# PantherZVS.net
KiCad netlist of a schematic drawn in Altium Designer
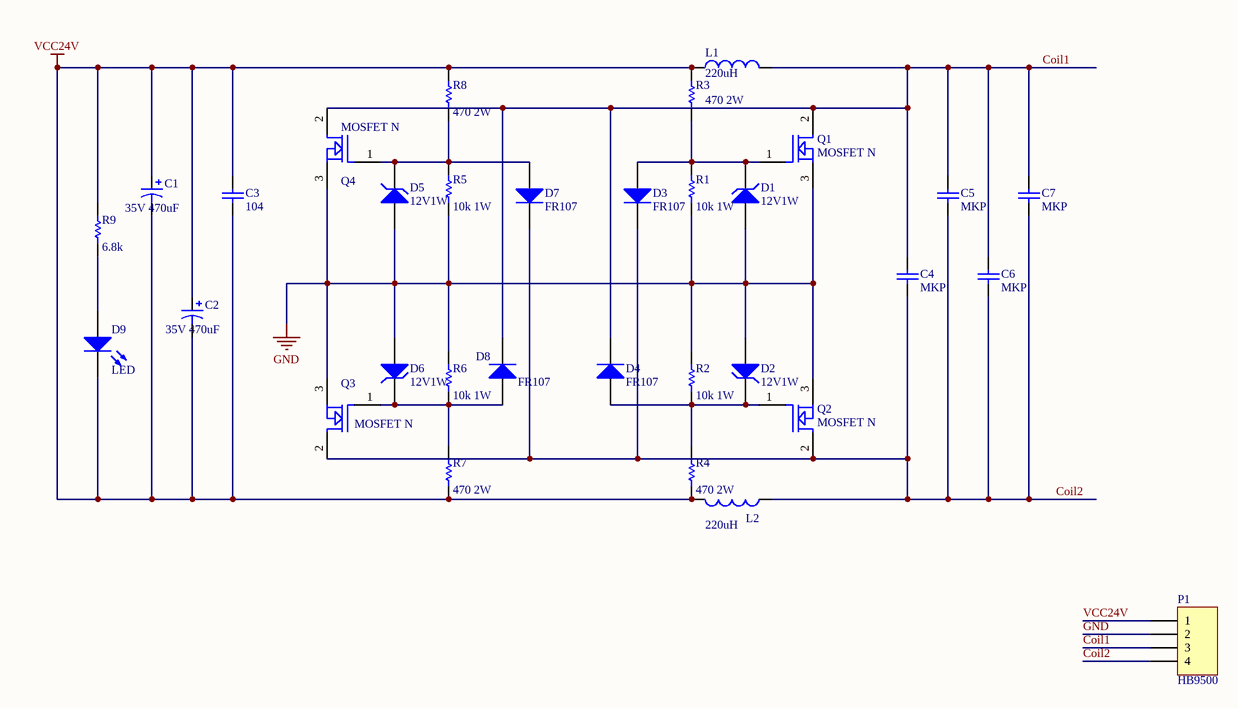
[diagram p0: PantherZVS.SchDoc]

(export (version "E")
  (design (tool "Eeschema 10.0.6"))
  (components
    (comp (ref "C1")
      (value "35V 470uF")
      (footprint "C4_5_10mm")
      (description "Polarized Capacitor (Radial)")
      (fields (field (name "PUBLISHER") "Altium Limited"))
      (libsource (lib "Miscellaneous Devices") (part "Cap Pol1"))
    )
    (comp (ref "C2")
      (value "35V 470uF")
      (footprint "C4_5_10mm")
      (description "Polarized Capacitor (Radial)")
      (fields (field (name "PUBLISHER") "Altium Limited"))
      (libsource (lib "Miscellaneous Devices") (part "Cap Pol1"))
    )
    (comp (ref "C3")
      (value "104")
      (footprint "RAD-0.3")
      (description "Capacitor")
      (fields (field (name "PUBLISHER") "Altium Limited"))
      (libsource (lib "Miscellaneous Devices") (part "Cap"))
    )
    (comp (ref "C4")
      (value "MKP")
      (footprint "MKP_Capacitor")
      (description "Capacitor")
      (fields (field (name "PUBLISHER") "Altium Limited"))
      (libsource (lib "Miscellaneous Devices") (part "Cap"))
    )
    (comp (ref "C5")
      (value "MKP")
      (footprint "MKP_Capacitor")
      (description "Capacitor")
      (fields (field (name "PUBLISHER") "Altium Limited"))
      (libsource (lib "Miscellaneous Devices") (part "Cap"))
    )
    (comp (ref "C6")
      (value "MKP")
      (footprint "MKP_Capacitor")
      (description "Capacitor")
      (fields (field (name "PUBLISHER") "Altium Limited"))
      (libsource (lib "Miscellaneous Devices") (part "Cap"))
    )
    (comp (ref "C7")
      (value "MKP")
      (footprint "MKP_Capacitor")
      (description "Capacitor")
      (fields (field (name "PUBLISHER") "Altium Limited"))
      (libsource (lib "Miscellaneous Devices") (part "Cap"))
    )
    (comp (ref "D1")
      (value "12V1W")
      (footprint "DIODE-0.4")
      (description "Zener Diode")
      (fields (field (name "PUBLISHER") "Altium Limited"))
      (libsource (lib "Miscellaneous Devices") (part "D Zener"))
    )
    (comp (ref "D2")
      (value "12V1W")
      (footprint "DIODE-0.4")
      (description "Zener Diode")
      (fields (field (name "PUBLISHER") "Altium Limited"))
      (libsource (lib "Miscellaneous Devices") (part "D Zener"))
    )
    (comp (ref "D3")
      (value "FR107")
      (footprint "DIODE-0.4")
      (description "1 Amp General Purpose Rectifier")
      (fields (field (name "PUBLISHER") "Altium Limited"))
      (libsource (lib "Miscellaneous Devices") (part "Diode 1N4001"))
    )
    (comp (ref "D4")
      (value "FR107")
      (footprint "DIODE-0.4")
      (description "1 Amp General Purpose Rectifier")
      (fields (field (name "PUBLISHER") "Altium Limited"))
      (libsource (lib "Miscellaneous Devices") (part "Diode 1N4001"))
    )
    (comp (ref "D5")
      (value "12V1W")
      (footprint "DIODE-0.4")
      (description "Zener Diode")
      (fields (field (name "PUBLISHER") "Altium Limited"))
      (libsource (lib "Miscellaneous Devices") (part "D Zener"))
    )
    (comp (ref "D6")
      (value "12V1W")
      (footprint "DIODE-0.4")
      (description "Zener Diode")
      (fields (field (name "PUBLISHER") "Altium Limited"))
      (libsource (lib "Miscellaneous Devices") (part "D Zener"))
    )
    (comp (ref "D7")
      (value "FR107")
      (footprint "DIODE-0.4")
      (description "1 Amp General Purpose Rectifier")
      (fields (field (name "PUBLISHER") "Altium Limited"))
      (libsource (lib "Miscellaneous Devices") (part "Diode 1N4001"))
    )
    (comp (ref "D8")
      (value "FR107")
      (footprint "DIODE-0.4")
      (description "1 Amp General Purpose Rectifier")
      (fields (field (name "PUBLISHER") "Altium Limited"))
      (libsource (lib "Miscellaneous Devices") (part "Diode 1N4001"))
    )
    (comp (ref "D9")
      (value "LED")
      (footprint "0805")
      (description "Typical INFRARED GaAs LED")
      (fields (field (name "PUBLISHER") "Altium Limited"))
      (libsource (lib "Miscellaneous Devices") (part "LED0"))
    )
    (comp (ref "L1")
      (value "220uH")
      (footprint "HBL_30_10_H")
      (description "Inductor")
      (fields (field (name "PUBLISHER") "Altium Limited"))
      (libsource (lib "Miscellaneous Devices") (part "Inductor"))
    )
    (comp (ref "L2")
      (value "220uH")
      (footprint "HBL_30_10_H")
      (description "Inductor")
      (fields (field (name "PUBLISHER") "Altium Limited"))
      (libsource (lib "Miscellaneous Devices") (part "Inductor"))
    )
    (comp (ref "P1")
      (value "HB9500")
      (footprint "HB9500_4P")
      (description "Header, 4-Pin")
      (fields (field (name "PUBLISHER") "Altium Limited"))
      (libsource (lib "Miscellaneous Connectors") (part "Header 4"))
    )
    (comp (ref "Q1")
      (value "MOSFET N")
      (footprint "TO-247AC_ZCEDGE")
      (libsource (lib "场效应管及可控硅") (part "MOSFET N"))
    )
    (comp (ref "Q2")
      (value "MOSFET N")
      (footprint "TO-247AC_ZCEDGE")
      (libsource (lib "场效应管及可控硅") (part "MOSFET N"))
    )
    (comp (ref "Q3")
      (value "MOSFET N")
      (footprint "TO-247AC_ZCEDGE")
      (libsource (lib "场效应管及可控硅") (part "MOSFET N"))
    )
    (comp (ref "Q4")
      (value "MOSFET N")
      (footprint "TO-247AC_ZCEDGE")
      (libsource (lib "场效应管及可控硅") (part "MOSFET N"))
    )
    (comp (ref "R1")
      (value "10k 1W")
      (footprint "1WZC")
      (description "Resistor")
      (fields (field (name "PUBLISHER") "Altium Limited"))
      (libsource (lib "Miscellaneous Devices") (part "Res1"))
    )
    (comp (ref "R2")
      (value "10k 1W")
      (footprint "1WZC")
      (description "Resistor")
      (fields (field (name "PUBLISHER") "Altium Limited"))
      (libsource (lib "Miscellaneous Devices") (part "Res1"))
    )
    (comp (ref "R3")
      (value "470 2W")
      (footprint "1WZC")
      (description "Resistor")
      (fields (field (name "PUBLISHER") "Altium Limited"))
      (libsource (lib "Miscellaneous Devices") (part "Res1"))
    )
    (comp (ref "R4")
      (value "470 2W")
      (footprint "2WZC")
      (description "Resistor")
      (fields (field (name "PUBLISHER") "Altium Limited"))
      (libsource (lib "Miscellaneous Devices") (part "Res1"))
    )
    (comp (ref "R5")
      (value "10k 1W")
      (footprint "1WZC")
      (description "Resistor")
      (fields (field (name "PUBLISHER") "Altium Limited"))
      (libsource (lib "Miscellaneous Devices") (part "Res1"))
    )
    (comp (ref "R6")
      (value "10k 1W")
      (footprint "1WZC")
      (description "Resistor")
      (fields (field (name "PUBLISHER") "Altium Limited"))
      (libsource (lib "Miscellaneous Devices") (part "Res1"))
    )
    (comp (ref "R7")
      (value "470 2W")
      (footprint "2WZC")
      (description "Resistor")
      (fields (field (name "PUBLISHER") "Altium Limited"))
      (libsource (lib "Miscellaneous Devices") (part "Res1"))
    )
    (comp (ref "R8")
      (value "470 2W")
      (footprint "2WZC")
      (description "Resistor")
      (fields (field (name "PUBLISHER") "Altium Limited"))
      (libsource (lib "Miscellaneous Devices") (part "Res1"))
    )
    (comp (ref "R9")
      (value "6.8k")
      (footprint "AXIAL-0.3")
      (description "Resistor")
      (fields (field (name "PUBLISHER") "Altium Limited"))
      (libsource (lib "Miscellaneous Devices") (part "Res1"))
    )
  )
  (nets
    (net (code "1") (name "/Coil1") (class "Default")
      (node (ref "C4") (pin "2") (pinfunction "2_2") (pintype "passive"))
      (node (ref "C5") (pin "2") (pinfunction "2_2") (pintype "passive"))
      (node (ref "C6") (pin "2") (pinfunction "2_2") (pintype "passive"))
      (node (ref "C7") (pin "2") (pinfunction "2_2") (pintype "passive"))
      (node (ref "D4") (pin "2") (pinfunction "K_2") (pintype "passive"))
      (node (ref "D8") (pin "2") (pinfunction "K_2") (pintype "passive"))
      (node (ref "L1") (pin "2") (pinfunction "2_2") (pintype "passive"))
      (node (ref "P1") (pin "3") (pinfunction "3_3") (pintype "passive"))
      (node (ref "Q1") (pin "2") (pinfunction "D_2") (pintype "passive"))
      (node (ref "Q4") (pin "2") (pinfunction "D_2") (pintype "passive"))
    )
    (net (code "2") (name "/Coil2") (class "Default")
      (node (ref "C4") (pin "1") (pinfunction "1_1") (pintype "passive"))
      (node (ref "C5") (pin "1") (pinfunction "1_1") (pintype "passive"))
      (node (ref "C6") (pin "1") (pinfunction "1_1") (pintype "passive"))
      (node (ref "C7") (pin "1") (pinfunction "1_1") (pintype "passive"))
      (node (ref "D3") (pin "2") (pinfunction "K_2") (pintype "passive"))
      (node (ref "D7") (pin "2") (pinfunction "K_2") (pintype "passive"))
      (node (ref "L2") (pin "1") (pinfunction "1_1") (pintype "passive"))
      (node (ref "P1") (pin "4") (pinfunction "4_4") (pintype "passive"))
      (node (ref "Q2") (pin "2") (pinfunction "D_2") (pintype "passive"))
      (node (ref "Q3") (pin "2") (pinfunction "D_2") (pintype "passive"))
    )
    (net (code "3") (name "GND") (class "Default")
      (node (ref "D1") (pin "1") (pinfunction "A_1") (pintype "passive"))
      (node (ref "D2") (pin "1") (pinfunction "A_1") (pintype "passive"))
      (node (ref "D5") (pin "1") (pinfunction "A_1") (pintype "passive"))
      (node (ref "D6") (pin "1") (pinfunction "A_1") (pintype "passive"))
      (node (ref "P1") (pin "2") (pinfunction "2_2") (pintype "passive"))
      (node (ref "Q1") (pin "3") (pinfunction "S_3") (pintype "passive"))
      (node (ref "Q2") (pin "3") (pinfunction "S_3") (pintype "passive"))
      (node (ref "Q3") (pin "3") (pinfunction "S_3") (pintype "passive"))
      (node (ref "Q4") (pin "3") (pinfunction "S_3") (pintype "passive"))
      (node (ref "R1") (pin "1") (pinfunction "1_1") (pintype "passive"))
      (node (ref "R2") (pin "2") (pinfunction "2_2") (pintype "passive"))
      (node (ref "R5") (pin "2") (pinfunction "2_2") (pintype "passive"))
      (node (ref "R6") (pin "1") (pinfunction "1_1") (pintype "passive"))
    )
    (net (code "4") (name "Net-(D1-K)") (class "Default")
      (node (ref "D1") (pin "2") (pinfunction "K_2") (pintype "passive"))
      (node (ref "D3") (pin "1") (pinfunction "A_1") (pintype "passive"))
      (node (ref "Q1") (pin "1") (pinfunction "G_1") (pintype "passive"))
      (node (ref "R1") (pin "2") (pinfunction "2_2") (pintype "passive"))
      (node (ref "R3") (pin "1") (pinfunction "1_1") (pintype "passive"))
    )
    (net (code "5") (name "Net-(D2-K)") (class "Default")
      (node (ref "D2") (pin "2") (pinfunction "K_2") (pintype "passive"))
      (node (ref "D4") (pin "1") (pinfunction "A_1") (pintype "passive"))
      (node (ref "Q2") (pin "1") (pinfunction "G_1") (pintype "passive"))
      (node (ref "R2") (pin "1") (pinfunction "1_1") (pintype "passive"))
      (node (ref "R4") (pin "2") (pinfunction "2_2") (pintype "passive"))
    )
    (net (code "6") (name "Net-(D5-K)") (class "Default")
      (node (ref "D5") (pin "2") (pinfunction "K_2") (pintype "passive"))
      (node (ref "D7") (pin "1") (pinfunction "A_1") (pintype "passive"))
      (node (ref "Q4") (pin "1") (pinfunction "G_1") (pintype "passive"))
      (node (ref "R5") (pin "1") (pinfunction "1_1") (pintype "passive"))
      (node (ref "R8") (pin "2") (pinfunction "2_2") (pintype "passive"))
    )
    (net (code "7") (name "Net-(D6-K)") (class "Default")
      (node (ref "D6") (pin "2") (pinfunction "K_2") (pintype "passive"))
      (node (ref "D8") (pin "1") (pinfunction "A_1") (pintype "passive"))
      (node (ref "Q3") (pin "1") (pinfunction "G_1") (pintype "passive"))
      (node (ref "R6") (pin "2") (pinfunction "2_2") (pintype "passive"))
      (node (ref "R7") (pin "1") (pinfunction "1_1") (pintype "passive"))
    )
    (net (code "8") (name "Net-(D9-A)") (class "Default")
      (node (ref "D9") (pin "1") (pinfunction "A_1") (pintype "passive"))
      (node (ref "R9") (pin "1") (pinfunction "1_1") (pintype "passive"))
    )
    (net (code "9") (name "VCC24V") (class "Default")
      (node (ref "C1") (pin "1") (pinfunction "1_1") (pintype "passive"))
      (node (ref "C1") (pin "2") (pinfunction "2_2") (pintype "passive"))
      (node (ref "C2") (pin "1") (pinfunction "1_1") (pintype "passive"))
      (node (ref "C2") (pin "2") (pinfunction "2_2") (pintype "passive"))
      (node (ref "C3") (pin "1") (pinfunction "1_1") (pintype "passive"))
      (node (ref "C3") (pin "2") (pinfunction "2_2") (pintype "passive"))
      (node (ref "D9") (pin "2") (pinfunction "K_2") (pintype "passive"))
      (node (ref "L1") (pin "1") (pinfunction "1_1") (pintype "passive"))
      (node (ref "L2") (pin "2") (pinfunction "2_2") (pintype "passive"))
      (node (ref "P1") (pin "1") (pinfunction "1_1") (pintype "passive"))
      (node (ref "R3") (pin "2") (pinfunction "2_2") (pintype "passive"))
      (node (ref "R4") (pin "1") (pinfunction "1_1") (pintype "passive"))
      (node (ref "R7") (pin "2") (pinfunction "2_2") (pintype "passive"))
      (node (ref "R8") (pin "1") (pinfunction "1_1") (pintype "passive"))
      (node (ref "R9") (pin "2") (pinfunction "2_2") (pintype "passive"))
    )
  )
)
